# digital_clock_no_res.net
KiCad netlist of a schematic drawn in EasyEDA
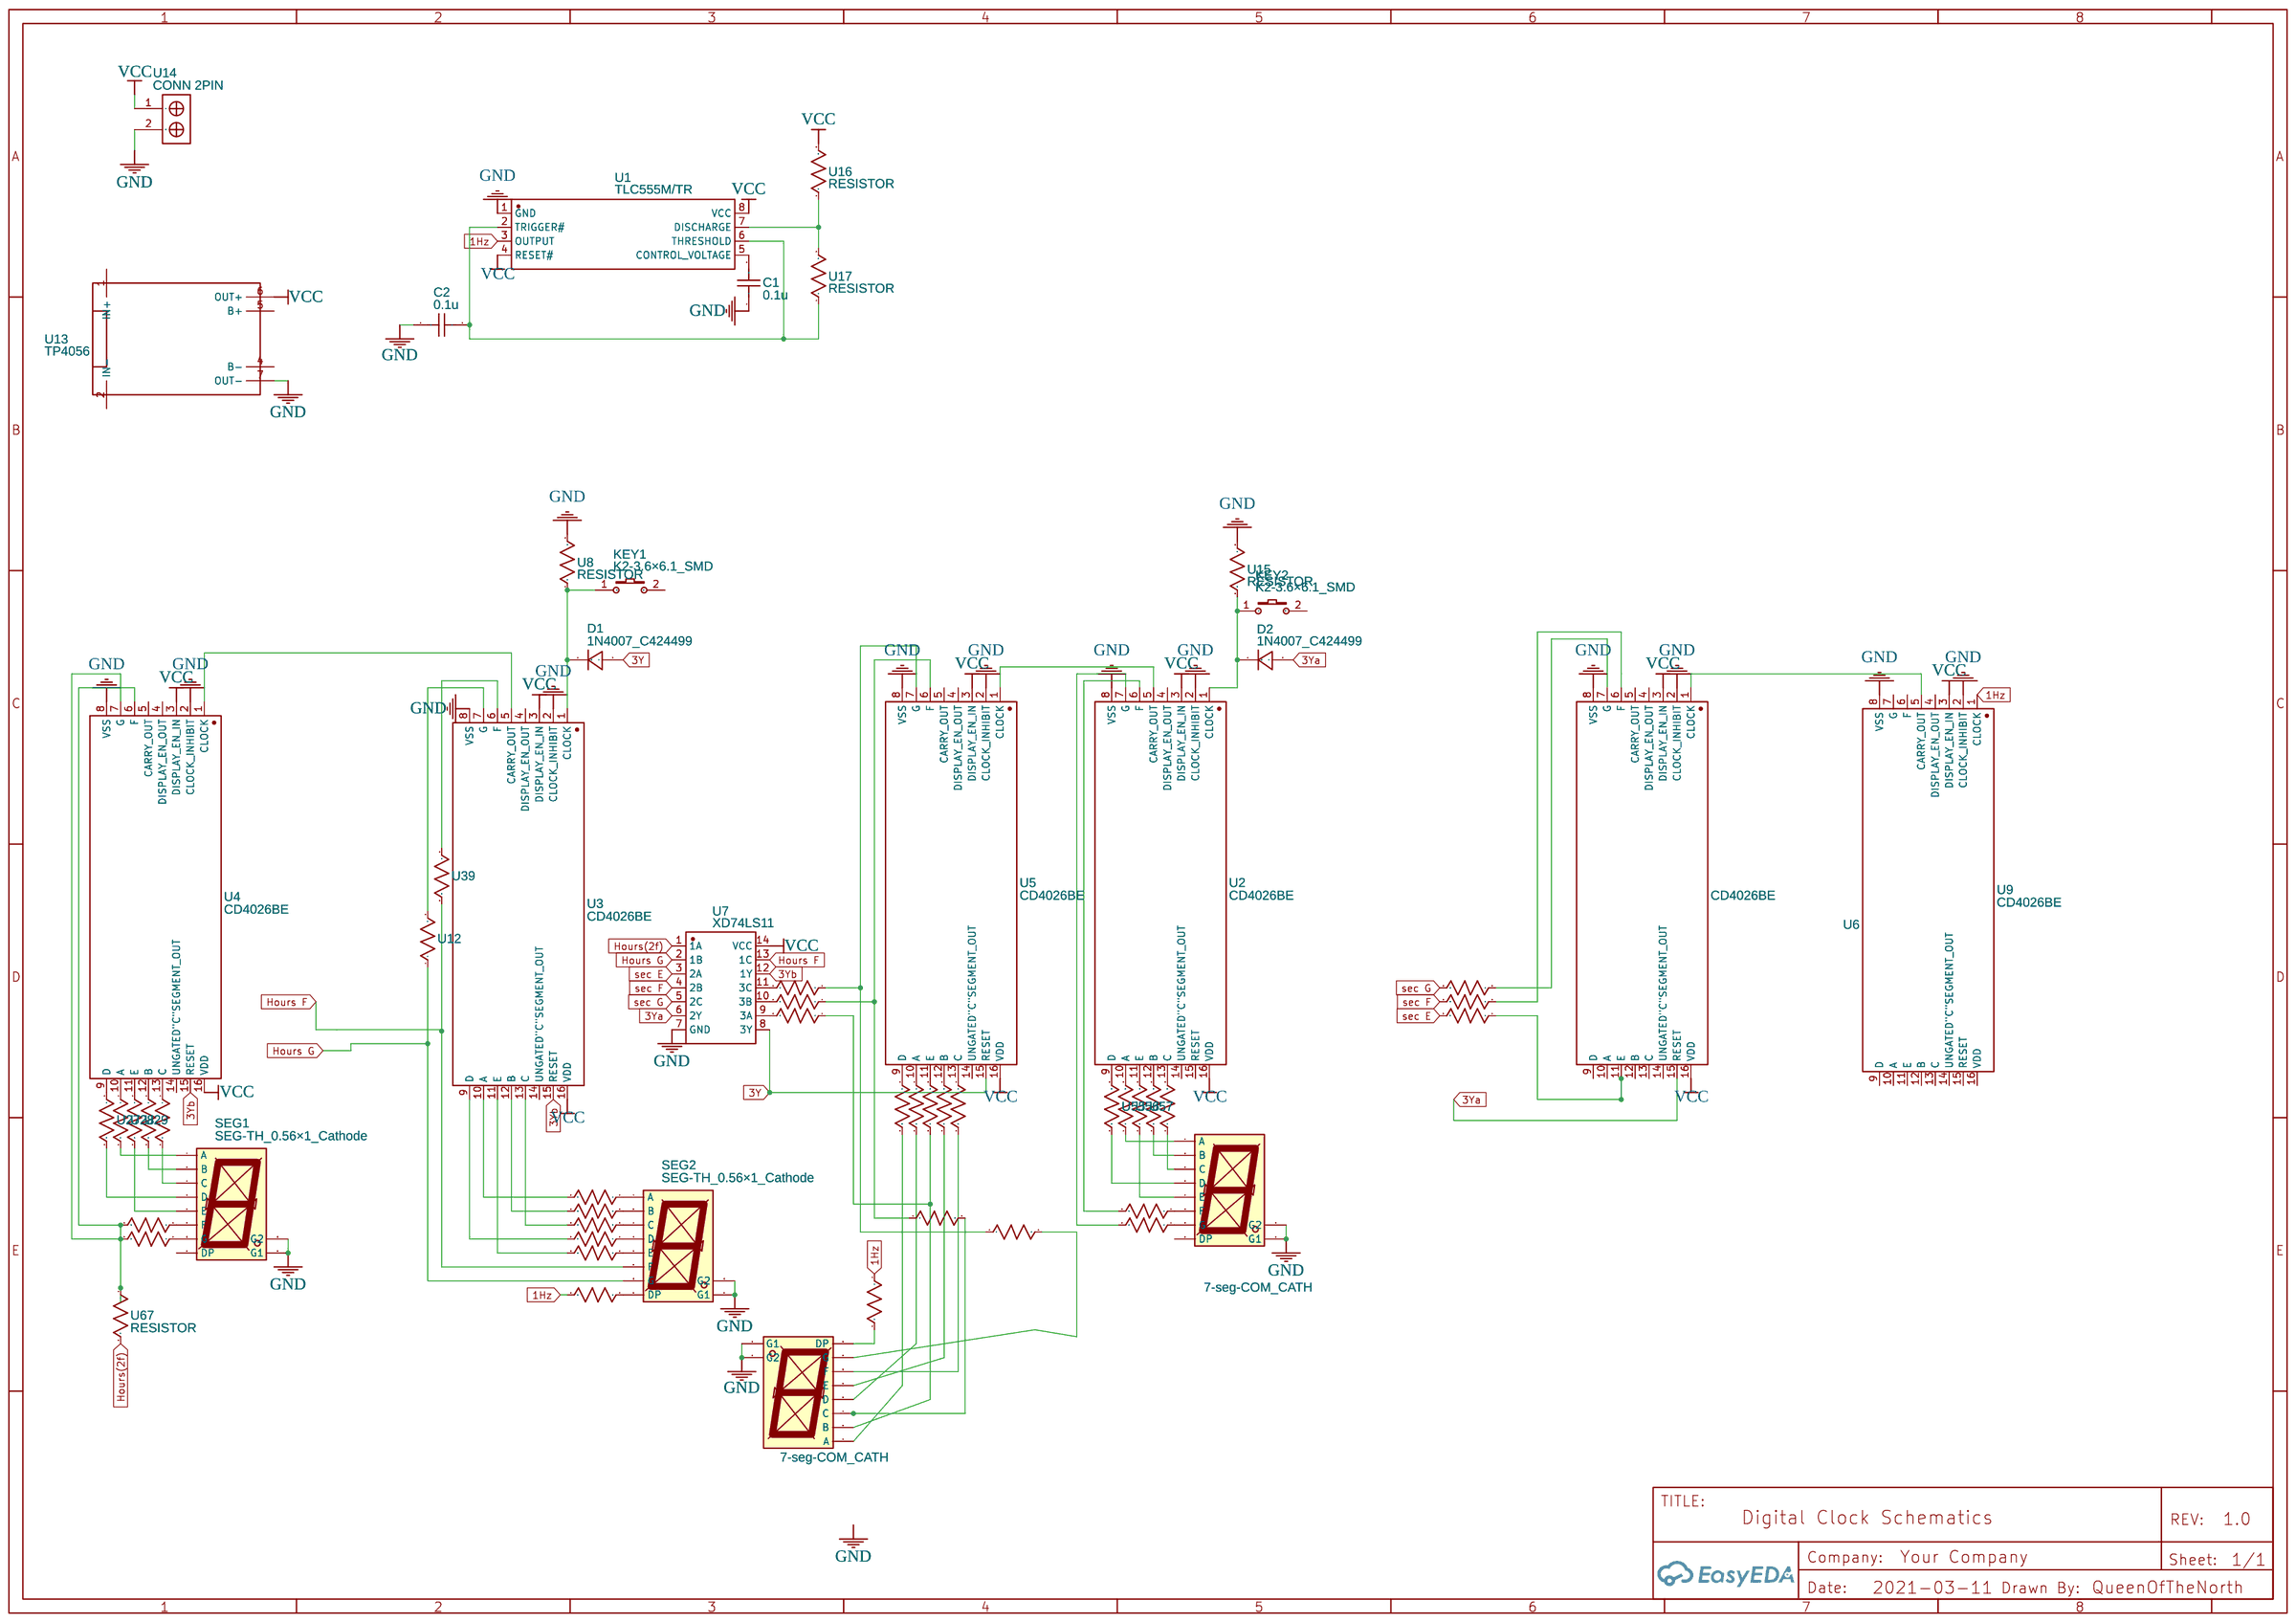
[diagram p0: schematic sheet]

(export (version "E")
  (design (tool "Eeschema 10.0.6"))
  (components
    (comp (ref "C1") (value "0.1u") (libsource (lib "") (part "C_0603_US")))
    (comp (ref "C2") (value "0.1u") (libsource (lib "") (part "C_0603_US_1")))
    (comp (ref "D1")
      (value "1N4007_C424499")
      (fields (field (name "BOM_Manufacturer Part") "1N4007") (field (name "BOM_Supplier Part") "C424499"))
      (libsource (lib "") (part "1N4007_C424499"))
    )
    (comp (ref "D2")
      (value "1N4007_C424499")
      (fields (field (name "BOM_Manufacturer Part") "1N4007") (field (name "BOM_Supplier Part") "C424499"))
      (libsource (lib "") (part "1N4007_C424499"))
    )
    (comp (ref "KEY1")
      (value "K2-3.6×6.1_SMD")
      (fields
        (field (name "BOM_Manufacturer Part") "K2-1107ST-A4SW-06")
        (field (name "BOM_Supplier Part") "C118141")
      )
      (libsource (lib "") (part "K2-3.6×6.1_SMD"))
    )
    (comp (ref "KEY2")
      (value "K2-3.6×6.1_SMD")
      (fields
        (field (name "BOM_Manufacturer Part") "K2-1107ST-A4SW-06")
        (field (name "BOM_Supplier Part") "C118141")
      )
      (libsource (lib "") (part "K2-3.6×6.1_SMD"))
    )
    (comp (ref "SEG1")
      (value "SEG-TH_0.56×1_Cathode")
      (fields (field (name "BOM_Supplier Part") "C8093"))
      (libsource (lib "") (part "SEG-TH_0.56×1_Cathode"))
    )
    (comp (ref "SEG2")
      (value "SEG-TH_0.56×1_Cathode")
      (fields (field (name "BOM_Supplier Part") "C8093"))
      (libsource (lib "") (part "SEG-TH_0.56×1_Cathode"))
    )
    (comp (ref "SEG3")
      (value "7-seg-COM_CATH")
      (fields (field (name "BOM_Supplier Part") "C8093"))
      (libsource (lib "") (part "SEG-TH_0.56×1_Cathode_1"))
    )
    (comp (ref "SEG4")
      (value "7-seg-COM_CATH")
      (fields (field (name "BOM_Supplier Part") "C8093"))
      (libsource (lib "") (part "SEG-TH_0.56×1_Cathode"))
    )
    (comp (ref "U1")
      (value "TLC555M/TR")
      (fields (field (name "BOM_Supplier Part") "C383061"))
      (libsource (lib "") (part "TLC555M/TR"))
    )
    (comp (ref "U2")
      (value "CD4026BE")
      (fields (field (name "BOM_Supplier Part") "C89909"))
      (libsource (lib "") (part "CD4026BE"))
    )
    (comp (ref "U3")
      (value "CD4026BE")
      (fields (field (name "BOM_Supplier Part") "C89909"))
      (libsource (lib "") (part "CD4026BE"))
    )
    (comp (ref "U4")
      (value "CD4026BE")
      (fields (field (name "BOM_Supplier Part") "C89909"))
      (libsource (lib "") (part "CD4026BE"))
    )
    (comp (ref "U5")
      (value "CD4026BE")
      (fields (field (name "BOM_Supplier Part") "C89909"))
      (libsource (lib "") (part "CD4026BE"))
    )
    (comp (ref "U6")
      (value "CD4026BE")
      (fields (field (name "BOM_Supplier Part") "C89909"))
      (libsource (lib "") (part "CD4026BE"))
    )
    (comp (ref "U7")
      (value "XD74LS11")
      (fields (field (name "BOM_Supplier Part") "C521167"))
      (libsource (lib "") (part "XD74LS11"))
    )
    (comp (ref "U8")
      (value "RESISTOR")
      (fields (field (name "BOM_Manufacturer Part") "0.4W 1% RESISTOR"))
      (libsource (lib "") (part "RESISTOR"))
    )
    (comp (ref "U9")
      (value "CD4026BE")
      (fields (field (name "BOM_Supplier Part") "C89909"))
      (libsource (lib "") (part "CD4026BE"))
    )
    (comp (ref "U10")
      (value "RESISTOR")
      (fields (field (name "BOM_Manufacturer Part") "0.4W 1% RESISTOR"))
      (libsource (lib "") (part "RESISTOR_7"))
    )
    (comp (ref "U11")
      (value "RESISTOR")
      (fields (field (name "BOM_Manufacturer Part") "0.4W 1% RESISTOR"))
      (libsource (lib "") (part "RESISTOR_3"))
    )
    (comp (ref "U12")
      (value "RESISTOR")
      (fields (field (name "BOM_Manufacturer Part") "0.4W 1% RESISTOR"))
      (libsource (lib "") (part "RESISTOR_2"))
    )
    (comp (ref "U13")
      (value "TP4056")
      (fields (field (name "BOM_Manufacturer Part") "TP4056-protect"))
      (libsource (lib "") (part "TP4056"))
    )
    (comp (ref "U14")
      (value "CONN 2PIN")
      (fields
        (field (name "BOM_Manufacturer Part") "Terminal Block")
        (field (name "BOM_Supplier Part") "undefined")
      )
      (libsource (lib "") (part "CONN 2PIN"))
    )
    (comp (ref "U15")
      (value "RESISTOR")
      (fields (field (name "BOM_Manufacturer Part") "0.4W 1% RESISTOR"))
      (libsource (lib "") (part "RESISTOR"))
    )
    (comp (ref "U16")
      (value "RESISTOR")
      (fields (field (name "BOM_Manufacturer Part") "0.4W 1% RESISTOR"))
      (libsource (lib "") (part "RESISTOR"))
    )
    (comp (ref "U17")
      (value "RESISTOR")
      (fields (field (name "BOM_Manufacturer Part") "0.4W 1% RESISTOR"))
      (libsource (lib "") (part "RESISTOR"))
    )
    (comp (ref "U18")
      (value "RESISTOR")
      (fields (field (name "BOM_Manufacturer Part") "0.4W 1% RESISTOR"))
      (libsource (lib "") (part "RESISTOR_3"))
    )
    (comp (ref "U19")
      (value "RESISTOR")
      (fields (field (name "BOM_Manufacturer Part") "0.4W 1% RESISTOR"))
      (libsource (lib "") (part "RESISTOR_3"))
    )
    (comp (ref "U20")
      (value "RESISTOR")
      (fields (field (name "BOM_Manufacturer Part") "0.4W 1% RESISTOR"))
      (libsource (lib "") (part "RESISTOR_3"))
    )
    (comp (ref "U21")
      (value "RESISTOR")
      (fields (field (name "BOM_Manufacturer Part") "0.4W 1% RESISTOR"))
      (libsource (lib "") (part "RESISTOR_3"))
    )
    (comp (ref "U22")
      (value "RESISTOR")
      (fields (field (name "BOM_Manufacturer Part") "0.4W 1% RESISTOR"))
      (libsource (lib "") (part "RESISTOR_3"))
    )
    (comp (ref "U25")
      (value "RESISTOR")
      (fields (field (name "BOM_Manufacturer Part") "0.4W 1% RESISTOR"))
      (libsource (lib "") (part "RESISTOR_3"))
    )
    (comp (ref "U26")
      (value "RESISTOR")
      (fields (field (name "BOM_Manufacturer Part") "0.4W 1% RESISTOR"))
      (libsource (lib "") (part "RESISTOR_3"))
    )
    (comp (ref "U27")
      (value "RESISTOR")
      (fields (field (name "BOM_Manufacturer Part") "0.4W 1% RESISTOR"))
      (libsource (lib "") (part "RESISTOR_4"))
    )
    (comp (ref "U28")
      (value "RESISTOR")
      (fields (field (name "BOM_Manufacturer Part") "0.4W 1% RESISTOR"))
      (libsource (lib "") (part "RESISTOR_4"))
    )
    (comp (ref "U29")
      (value "RESISTOR")
      (fields (field (name "BOM_Manufacturer Part") "0.4W 1% RESISTOR"))
      (libsource (lib "") (part "RESISTOR_4"))
    )
    (comp (ref "U30")
      (value "RESISTOR")
      (fields (field (name "BOM_Manufacturer Part") "0.4W 1% RESISTOR"))
      (libsource (lib "") (part "RESISTOR_4"))
    )
    (comp (ref "U31")
      (value "RESISTOR")
      (fields (field (name "BOM_Manufacturer Part") "0.4W 1% RESISTOR"))
      (libsource (lib "") (part "RESISTOR_4"))
    )
    (comp (ref "U32")
      (value "RESISTOR")
      (fields (field (name "BOM_Manufacturer Part") "0.4W 1% RESISTOR"))
      (libsource (lib "") (part "RESISTOR_4"))
    )
    (comp (ref "U33")
      (value "RESISTOR")
      (fields (field (name "BOM_Manufacturer Part") "0.4W 1% RESISTOR"))
      (libsource (lib "") (part "RESISTOR_4"))
    )
    (comp (ref "U34")
      (value "RESISTOR")
      (fields (field (name "BOM_Manufacturer Part") "0.4W 1% RESISTOR"))
      (libsource (lib "") (part "RESISTOR_4"))
    )
    (comp (ref "U35")
      (value "RESISTOR")
      (fields (field (name "BOM_Manufacturer Part") "0.4W 1% RESISTOR"))
      (libsource (lib "") (part "RESISTOR_4"))
    )
    (comp (ref "U36")
      (value "RESISTOR")
      (fields (field (name "BOM_Manufacturer Part") "0.4W 1% RESISTOR"))
      (libsource (lib "") (part "RESISTOR_4"))
    )
    (comp (ref "U37")
      (value "RESISTOR")
      (fields (field (name "BOM_Manufacturer Part") "0.4W 1% RESISTOR"))
      (libsource (lib "") (part "RESISTOR_1"))
    )
    (comp (ref "U38")
      (value "RESISTOR")
      (fields (field (name "BOM_Manufacturer Part") "0.4W 1% RESISTOR"))
      (libsource (lib "") (part "RESISTOR_1"))
    )
    (comp (ref "U39")
      (value "RESISTOR")
      (fields (field (name "BOM_Manufacturer Part") "0.4W 1% RESISTOR"))
      (libsource (lib "") (part "RESISTOR_2"))
    )
    (comp (ref "U52")
      (value "RESISTOR")
      (fields (field (name "BOM_Manufacturer Part") "0.4W 1% RESISTOR"))
      (libsource (lib "") (part "RESISTOR_3"))
    )
    (comp (ref "U53")
      (value "RESISTOR")
      (fields (field (name "BOM_Manufacturer Part") "0.4W 1% RESISTOR"))
      (libsource (lib "") (part "RESISTOR_3"))
    )
    (comp (ref "U54")
      (value "RESISTOR")
      (fields (field (name "BOM_Manufacturer Part") "0.4W 1% RESISTOR"))
      (libsource (lib "") (part "RESISTOR_3"))
    )
    (comp (ref "U55")
      (value "RESISTOR")
      (fields (field (name "BOM_Manufacturer Part") "0.4W 1% RESISTOR"))
      (libsource (lib "") (part "RESISTOR"))
    )
    (comp (ref "U56")
      (value "RESISTOR")
      (fields (field (name "BOM_Manufacturer Part") "0.4W 1% RESISTOR"))
      (libsource (lib "") (part "RESISTOR"))
    )
    (comp (ref "U57")
      (value "RESISTOR")
      (fields (field (name "BOM_Manufacturer Part") "0.4W 1% RESISTOR"))
      (libsource (lib "") (part "RESISTOR"))
    )
    (comp (ref "U58")
      (value "RESISTOR")
      (fields (field (name "BOM_Manufacturer Part") "0.4W 1% RESISTOR"))
      (libsource (lib "") (part "RESISTOR"))
    )
    (comp (ref "U59")
      (value "RESISTOR")
      (fields (field (name "BOM_Manufacturer Part") "0.4W 1% RESISTOR"))
      (libsource (lib "") (part "RESISTOR"))
    )
    (comp (ref "U60")
      (value "RESISTOR")
      (fields (field (name "BOM_Manufacturer Part") "0.4W 1% RESISTOR"))
      (libsource (lib "") (part "RESISTOR_3"))
    )
    (comp (ref "U61")
      (value "RESISTOR")
      (fields (field (name "BOM_Manufacturer Part") "0.4W 1% RESISTOR"))
      (libsource (lib "") (part "RESISTOR_3"))
    )
    (comp (ref "U62")
      (value "RESISTOR")
      (fields (field (name "BOM_Manufacturer Part") "0.4W 1% RESISTOR"))
      (libsource (lib "") (part "RESISTOR_5"))
    )
    (comp (ref "U63")
      (value "RESISTOR")
      (fields (field (name "BOM_Manufacturer Part") "0.4W 1% RESISTOR"))
      (libsource (lib "") (part "RESISTOR_5"))
    )
    (comp (ref "U64")
      (value "RESISTOR")
      (fields (field (name "BOM_Manufacturer Part") "0.4W 1% RESISTOR"))
      (libsource (lib "") (part "RESISTOR_5"))
    )
    (comp (ref "U67")
      (value "RESISTOR")
      (fields (field (name "BOM_Manufacturer Part") "0.4W 1% RESISTOR"))
      (libsource (lib "") (part "RESISTOR_6"))
    )
  )
  (nets
    (net (code "1") (name "1Hz") (class "Default")
      (node (ref "U1") (pin "3") (pinfunction "OUTPUT_3") (pintype "unspecified"))
      (node (ref "U10") (pin "1") (pinfunction "1_1") (pintype "unspecified"))
      (node (ref "U11") (pin "2") (pinfunction "2_2") (pintype "unspecified"))
      (node (ref "U9") (pin "1") (pinfunction "CLOCK_1") (pintype "unspecified"))
    )
    (net (code "2") (name "3Y") (class "Default")
      (node (ref "D1") (pin "2") (pinfunction "A_2") (pintype "unspecified"))
      (node (ref "U5") (pin "15") (pinfunction "RESET_15") (pintype "unspecified"))
      (node (ref "U7") (pin "8") (pinfunction "3Y_8") (pintype "unspecified"))
    )
    (net (code "3") (name "3Ya") (class "Default")
      (node (ref "D2") (pin "2") (pinfunction "A_2") (pintype "unspecified"))
      (node (ref "U6") (pin "15") (pinfunction "RESET_15") (pintype "unspecified"))
      (node (ref "U7") (pin "6") (pinfunction "2Y_6") (pintype "unspecified"))
    )
    (net (code "4") (name "3Yb") (class "Default")
      (node (ref "U3") (pin "15") (pinfunction "RESET_15") (pintype "unspecified"))
      (node (ref "U4") (pin "15") (pinfunction "RESET_15") (pintype "unspecified"))
      (node (ref "U7") (pin "12") (pinfunction "1Y_12") (pintype "unspecified"))
    )
    (net (code "5") (name "GND") (class "Default")
      (node (ref "C1") (pin "1") (pinfunction "1_1") (pintype "unspecified"))
      (node (ref "C2") (pin "1") (pinfunction "1_1") (pintype "unspecified"))
      (node (ref "SEG1") (pin "3") (pinfunction "G1_3") (pintype "unspecified"))
      (node (ref "SEG1") (pin "8") (pinfunction "G2_8") (pintype "unspecified"))
      (node (ref "SEG2") (pin "3") (pinfunction "G1_3") (pintype "unspecified"))
      (node (ref "SEG2") (pin "8") (pinfunction "G2_8") (pintype "unspecified"))
      (node (ref "SEG3") (pin "3") (pinfunction "G1_3") (pintype "unspecified"))
      (node (ref "SEG3") (pin "8") (pinfunction "G2_8") (pintype "unspecified"))
      (node (ref "SEG4") (pin "3") (pinfunction "G1_3") (pintype "unspecified"))
      (node (ref "SEG4") (pin "8") (pinfunction "G2_8") (pintype "unspecified"))
      (node (ref "U1") (pin "1") (pinfunction "GND_1") (pintype "unspecified"))
      (node (ref "U13") (pin "7") (pinfunction "OUT-_7") (pintype "unspecified"))
      (node (ref "U14") (pin "2") (pinfunction "2_2") (pintype "unspecified"))
      (node (ref "U15") (pin "2") (pinfunction "2_2") (pintype "unspecified"))
      (node (ref "U2") (pin "2") (pinfunction "CLOCK_INHIBIT_2") (pintype "unspecified"))
      (node (ref "U2") (pin "8") (pinfunction "VSS_8") (pintype "unspecified"))
      (node (ref "U3") (pin "2") (pinfunction "CLOCK_INHIBIT_2") (pintype "unspecified"))
      (node (ref "U3") (pin "8") (pinfunction "VSS_8") (pintype "unspecified"))
      (node (ref "U4") (pin "2") (pinfunction "CLOCK_INHIBIT_2") (pintype "unspecified"))
      (node (ref "U4") (pin "8") (pinfunction "VSS_8") (pintype "unspecified"))
      (node (ref "U5") (pin "2") (pinfunction "CLOCK_INHIBIT_2") (pintype "unspecified"))
      (node (ref "U5") (pin "8") (pinfunction "VSS_8") (pintype "unspecified"))
      (node (ref "U6") (pin "2") (pinfunction "CLOCK_INHIBIT_2") (pintype "unspecified"))
      (node (ref "U6") (pin "8") (pinfunction "VSS_8") (pintype "unspecified"))
      (node (ref "U7") (pin "7") (pinfunction "GND_7") (pintype "unspecified"))
      (node (ref "U8") (pin "2") (pinfunction "2_2") (pintype "unspecified"))
      (node (ref "U9") (pin "2") (pinfunction "CLOCK_INHIBIT_2") (pintype "unspecified"))
      (node (ref "U9") (pin "8") (pinfunction "VSS_8") (pintype "unspecified"))
    )
    (net (code "6") (name "Hours F") (class "Default")
      (node (ref "SEG2") (pin "9") (pinfunction "F_9") (pintype "unspecified"))
      (node (ref "U39") (pin "1") (pinfunction "1_1") (pintype "unspecified"))
      (node (ref "U7") (pin "13") (pinfunction "1C_13") (pintype "unspecified"))
    )
    (net (code "7") (name "Hours G") (class "Default")
      (node (ref "SEG2") (pin "10") (pinfunction "G_10") (pintype "unspecified"))
      (node (ref "U12") (pin "1") (pinfunction "1_1") (pintype "unspecified"))
      (node (ref "U7") (pin "2") (pinfunction "1B_2") (pintype "unspecified"))
    )
    (net (code "8") (name "Hours(2f)") (class "Default")
      (node (ref "U67") (pin "2") (pinfunction "2_2") (pintype "unspecified"))
      (node (ref "U7") (pin "1") (pinfunction "1A_1") (pintype "unspecified"))
    )
    (net (code "9") (name "Net-(D1-C)") (class "Default")
      (node (ref "D1") (pin "1") (pinfunction "C_1") (pintype "unspecified"))
      (node (ref "KEY1") (pin "1") (pinfunction "1_1") (pintype "unspecified"))
      (node (ref "U3") (pin "1") (pinfunction "CLOCK_1") (pintype "unspecified"))
      (node (ref "U8") (pin "1") (pinfunction "1_1") (pintype "unspecified"))
    )
    (net (code "10") (name "Net-(D2-C)") (class "Default")
      (node (ref "D2") (pin "1") (pinfunction "C_1") (pintype "unspecified"))
      (node (ref "KEY2") (pin "1") (pinfunction "1_1") (pintype "unspecified"))
      (node (ref "U15") (pin "1") (pinfunction "1_1") (pintype "unspecified"))
      (node (ref "U2") (pin "1") (pinfunction "CLOCK_1") (pintype "unspecified"))
    )
    (net (code "11") (name "Net-(SEG1-A)") (class "Default")
      (node (ref "SEG1") (pin "7") (pinfunction "A_7") (pintype "unspecified"))
      (node (ref "U28") (pin "2") (pinfunction "2_2") (pintype "unspecified"))
    )
    (net (code "12") (name "Net-(SEG1-B)") (class "Default")
      (node (ref "SEG1") (pin "6") (pinfunction "B_6") (pintype "unspecified"))
      (node (ref "U30") (pin "2") (pinfunction "2_2") (pintype "unspecified"))
    )
    (net (code "13") (name "Net-(SEG1-C)") (class "Default")
      (node (ref "SEG1") (pin "4") (pinfunction "C_4") (pintype "unspecified"))
      (node (ref "U31") (pin "2") (pinfunction "2_2") (pintype "unspecified"))
    )
    (net (code "14") (name "Net-(SEG1-D)") (class "Default")
      (node (ref "SEG1") (pin "2") (pinfunction "D_2") (pintype "unspecified"))
      (node (ref "U27") (pin "2") (pinfunction "2_2") (pintype "unspecified"))
    )
    (net (code "15") (name "Net-(SEG1-E)") (class "Default")
      (node (ref "SEG1") (pin "1") (pinfunction "E_1") (pintype "unspecified"))
      (node (ref "U29") (pin "2") (pinfunction "2_2") (pintype "unspecified"))
    )
    (net (code "16") (name "Net-(SEG1-F)") (class "Default")
      (node (ref "SEG1") (pin "9") (pinfunction "F_9") (pintype "unspecified"))
      (node (ref "U26") (pin "1") (pinfunction "1_1") (pintype "unspecified"))
    )
    (net (code "17") (name "Net-(SEG1-G)") (class "Default")
      (node (ref "SEG1") (pin "10") (pinfunction "G_10") (pintype "unspecified"))
      (node (ref "U25") (pin "1") (pinfunction "1_1") (pintype "unspecified"))
    )
    (net (code "18") (name "Net-(SEG2-A)") (class "Default")
      (node (ref "SEG2") (pin "7") (pinfunction "A_7") (pintype "unspecified"))
      (node (ref "U18") (pin "1") (pinfunction "1_1") (pintype "unspecified"))
    )
    (net (code "19") (name "Net-(SEG2-B)") (class "Default")
      (node (ref "SEG2") (pin "6") (pinfunction "B_6") (pintype "unspecified"))
      (node (ref "U19") (pin "1") (pinfunction "1_1") (pintype "unspecified"))
    )
    (net (code "20") (name "Net-(SEG2-C)") (class "Default")
      (node (ref "SEG2") (pin "4") (pinfunction "C_4") (pintype "unspecified"))
      (node (ref "U20") (pin "1") (pinfunction "1_1") (pintype "unspecified"))
    )
    (net (code "21") (name "Net-(SEG2-D)") (class "Default")
      (node (ref "SEG2") (pin "2") (pinfunction "D_2") (pintype "unspecified"))
      (node (ref "U21") (pin "1") (pinfunction "1_1") (pintype "unspecified"))
    )
    (net (code "22") (name "Net-(SEG2-DP)") (class "Default")
      (node (ref "SEG2") (pin "5") (pinfunction "DP_5") (pintype "unspecified"))
      (node (ref "U11") (pin "1") (pinfunction "1_1") (pintype "unspecified"))
    )
    (net (code "23") (name "Net-(SEG2-E)") (class "Default")
      (node (ref "SEG2") (pin "1") (pinfunction "E_1") (pintype "unspecified"))
      (node (ref "U22") (pin "1") (pinfunction "1_1") (pintype "unspecified"))
    )
    (net (code "24") (name "Net-(SEG3-A)") (class "Default")
      (node (ref "SEG3") (pin "7") (pinfunction "A_7") (pintype "unspecified"))
      (node (ref "U36") (pin "2") (pinfunction "2_2") (pintype "unspecified"))
    )
    (net (code "25") (name "Net-(SEG3-B)") (class "Default")
      (node (ref "SEG3") (pin "6") (pinfunction "B_6") (pintype "unspecified"))
      (node (ref "U34") (pin "2") (pinfunction "2_2") (pintype "unspecified"))
      (node (ref "U64") (pin "1") (pinfunction "1_1") (pintype "unspecified"))
    )
    (net (code "26") (name "Net-(SEG3-C)") (class "Default")
      (node (ref "SEG3") (pin "4") (pinfunction "C_4") (pintype "unspecified"))
      (node (ref "U37") (pin "2") (pinfunction "2_2") (pintype "unspecified"))
    )
    (net (code "27") (name "Net-(SEG3-D)") (class "Default")
      (node (ref "SEG3") (pin "2") (pinfunction "D_2") (pintype "unspecified"))
      (node (ref "U35") (pin "2") (pinfunction "2_2") (pintype "unspecified"))
    )
    (net (code "28") (name "Net-(SEG3-DP)") (class "Default")
      (node (ref "SEG3") (pin "5") (pinfunction "DP_5") (pintype "unspecified"))
      (node (ref "U10") (pin "2") (pinfunction "2_2") (pintype "unspecified"))
    )
    (net (code "29") (name "Net-(SEG3-E)") (class "Default")
      (node (ref "SEG3") (pin "1") (pinfunction "E_1") (pintype "unspecified"))
      (node (ref "U33") (pin "2") (pinfunction "2_2") (pintype "unspecified"))
    )
    (net (code "30") (name "Net-(SEG3-F)") (class "Default")
      (node (ref "SEG3") (pin "9") (pinfunction "F_9") (pintype "unspecified"))
      (node (ref "U32") (pin "2") (pinfunction "2_2") (pintype "unspecified"))
    )
    (net (code "31") (name "Net-(SEG3-G)") (class "Default")
      (node (ref "SEG3") (pin "10") (pinfunction "G_10") (pintype "unspecified"))
      (node (ref "U38") (pin "2") (pinfunction "2_2") (pintype "unspecified"))
    )
    (net (code "32") (name "Net-(SEG4-A)") (class "Default")
      (node (ref "SEG4") (pin "7") (pinfunction "A_7") (pintype "unspecified"))
      (node (ref "U56") (pin "1") (pinfunction "1_1") (pintype "unspecified"))
    )
    (net (code "33") (name "Net-(SEG4-B)") (class "Default")
      (node (ref "SEG4") (pin "6") (pinfunction "B_6") (pintype "unspecified"))
      (node (ref "U58") (pin "1") (pinfunction "1_1") (pintype "unspecified"))
    )
    (net (code "34") (name "Net-(SEG4-C)") (class "Default")
      (node (ref "SEG4") (pin "4") (pinfunction "C_4") (pintype "unspecified"))
      (node (ref "U59") (pin "1") (pinfunction "1_1") (pintype "unspecified"))
    )
    (net (code "35") (name "Net-(SEG4-D)") (class "Default")
      (node (ref "SEG4") (pin "2") (pinfunction "D_2") (pintype "unspecified"))
      (node (ref "U55") (pin "1") (pinfunction "1_1") (pintype "unspecified"))
    )
    (net (code "36") (name "Net-(SEG4-E)") (class "Default")
      (node (ref "SEG4") (pin "1") (pinfunction "E_1") (pintype "unspecified"))
      (node (ref "U57") (pin "1") (pinfunction "1_1") (pintype "unspecified"))
    )
    (net (code "37") (name "Net-(SEG4-F)") (class "Default")
      (node (ref "SEG4") (pin "9") (pinfunction "F_9") (pintype "unspecified"))
      (node (ref "U61") (pin "1") (pinfunction "1_1") (pintype "unspecified"))
    )
    (net (code "38") (name "Net-(SEG4-G)") (class "Default")
      (node (ref "SEG4") (pin "10") (pinfunction "G_10") (pintype "unspecified"))
      (node (ref "U60") (pin "1") (pinfunction "1_1") (pintype "unspecified"))
    )
    (net (code "39") (name "Net-(U1-CONTROL_VOLTAGE)") (class "Default")
      (node (ref "C1") (pin "2") (pinfunction "2_2") (pintype "unspecified"))
      (node (ref "U1") (pin "5") (pinfunction "CONTROL_VOLTAGE_5") (pintype "unspecified"))
    )
    (net (code "40") (name "Net-(U1-DISCHARGE)") (class "Default")
      (node (ref "U1") (pin "7") (pinfunction "DISCHARGE_7") (pintype "unspecified"))
      (node (ref "U16") (pin "1") (pinfunction "1_1") (pintype "unspecified"))
      (node (ref "U17") (pin "2") (pinfunction "2_2") (pintype "unspecified"))
    )
    (net (code "41") (name "Net-(U1-THRESHOLD)") (class "Default")
      (node (ref "C2") (pin "2") (pinfunction "2_2") (pintype "unspecified"))
      (node (ref "U1") (pin "2") (pinfunction "TRIGGER#_2") (pintype "unspecified"))
      (node (ref "U1") (pin "6") (pinfunction "THRESHOLD_6") (pintype "unspecified"))
      (node (ref "U17") (pin "1") (pinfunction "1_1") (pintype "unspecified"))
    )
    (net (code "42") (name "Net-(U2-A)") (class "Default")
      (node (ref "U2") (pin "10") (pinfunction "A_10") (pintype "unspecified"))
      (node (ref "U56") (pin "2") (pinfunction "2_2") (pintype "unspecified"))
    )
    (net (code "43") (name "Net-(U2-B)") (class "Default")
      (node (ref "U2") (pin "12") (pinfunction "B_12") (pintype "unspecified"))
      (node (ref "U58") (pin "2") (pinfunction "2_2") (pintype "unspecified"))
    )
    (net (code "44") (name "Net-(U2-C)") (class "Default")
      (node (ref "U2") (pin "13") (pinfunction "C_13") (pintype "unspecified"))
      (node (ref "U59") (pin "2") (pinfunction "2_2") (pintype "unspecified"))
    )
    (net (code "45") (name "Net-(U2-CARRY_OUT)") (class "Default")
      (node (ref "U2") (pin "5") (pinfunction "CARRY_OUT_5") (pintype "unspecified"))
      (node (ref "U5") (pin "1") (pinfunction "CLOCK_1") (pintype "unspecified"))
    )
    (net (code "46") (name "Net-(U2-D)") (class "Default")
      (node (ref "U2") (pin "9") (pinfunction "D_9") (pintype "unspecified"))
      (node (ref "U55") (pin "2") (pinfunction "2_2") (pintype "unspecified"))
    )
    (net (code "47") (name "Net-(U2-E)") (class "Default")
      (node (ref "U2") (pin "11") (pinfunction "E_11") (pintype "unspecified"))
      (node (ref "U57") (pin "2") (pinfunction "2_2") (pintype "unspecified"))
    )
    (net (code "48") (name "Net-(U2-F)") (class "Default")
      (node (ref "U2") (pin "6") (pinfunction "F_6") (pintype "unspecified"))
      (node (ref "U61") (pin "2") (pinfunction "2_2") (pintype "unspecified"))
    )
    (net (code "49") (name "Net-(U2-G)") (class "Default")
      (node (ref "U2") (pin "7") (pinfunction "G_7") (pintype "unspecified"))
      (node (ref "U60") (pin "2") (pinfunction "2_2") (pintype "unspecified"))
    )
    (net (code "50") (name "Net-(U3-A)") (class "Default")
      (node (ref "U18") (pin "2") (pinfunction "2_2") (pintype "unspecified"))
      (node (ref "U3") (pin "10") (pinfunction "A_10") (pintype "unspecified"))
    )
    (net (code "51") (name "Net-(U3-B)") (class "Default")
      (node (ref "U19") (pin "2") (pinfunction "2_2") (pintype "unspecified"))
      (node (ref "U3") (pin "12") (pinfunction "B_12") (pintype "unspecified"))
    )
    (net (code "52") (name "Net-(U3-C)") (class "Default")
      (node (ref "U20") (pin "2") (pinfunction "2_2") (pintype "unspecified"))
      (node (ref "U3") (pin "13") (pinfunction "C_13") (pintype "unspecified"))
    )
    (net (code "53") (name "Net-(U3-CARRY_OUT)") (class "Default")
      (node (ref "U3") (pin "5") (pinfunction "CARRY_OUT_5") (pintype "unspecified"))
      (node (ref "U4") (pin "1") (pinfunction "CLOCK_1") (pintype "unspecified"))
    )
    (net (code "54") (name "Net-(U3-D)") (class "Default")
      (node (ref "U21") (pin "2") (pinfunction "2_2") (pintype "unspecified"))
      (node (ref "U3") (pin "9") (pinfunction "D_9") (pintype "unspecified"))
    )
    (net (code "55") (name "Net-(U3-E)") (class "Default")
      (node (ref "U22") (pin "2") (pinfunction "2_2") (pintype "unspecified"))
      (node (ref "U3") (pin "11") (pinfunction "E_11") (pintype "unspecified"))
    )
    (net (code "56") (name "Net-(U3-F)") (class "Default")
      (node (ref "U3") (pin "6") (pinfunction "F_6") (pintype "unspecified"))
      (node (ref "U39") (pin "2") (pinfunction "2_2") (pintype "unspecified"))
    )
    (net (code "57") (name "Net-(U3-G)") (class "Default")
      (node (ref "U12") (pin "2") (pinfunction "2_2") (pintype "unspecified"))
      (node (ref "U3") (pin "7") (pinfunction "G_7") (pintype "unspecified"))
    )
    (net (code "58") (name "Net-(U4-A)") (class "Default")
      (node (ref "U28") (pin "1") (pinfunction "1_1") (pintype "unspecified"))
      (node (ref "U4") (pin "10") (pinfunction "A_10") (pintype "unspecified"))
    )
    (net (code "59") (name "Net-(U4-B)") (class "Default")
      (node (ref "U30") (pin "1") (pinfunction "1_1") (pintype "unspecified"))
      (node (ref "U4") (pin "12") (pinfunction "B_12") (pintype "unspecified"))
    )
    (net (code "60") (name "Net-(U4-C)") (class "Default")
      (node (ref "U31") (pin "1") (pinfunction "1_1") (pintype "unspecified"))
      (node (ref "U4") (pin "13") (pinfunction "C_13") (pintype "unspecified"))
    )
    (net (code "61") (name "Net-(U4-D)") (class "Default")
      (node (ref "U27") (pin "1") (pinfunction "1_1") (pintype "unspecified"))
      (node (ref "U4") (pin "9") (pinfunction "D_9") (pintype "unspecified"))
    )
    (net (code "62") (name "Net-(U4-E)") (class "Default")
      (node (ref "U29") (pin "1") (pinfunction "1_1") (pintype "unspecified"))
      (node (ref "U4") (pin "11") (pinfunction "E_11") (pintype "unspecified"))
    )
    (net (code "63") (name "Net-(U4-F)") (class "Default")
      (node (ref "U25") (pin "2") (pinfunction "2_2") (pintype "unspecified"))
      (node (ref "U26") (pin "2") (pinfunction "2_2") (pintype "unspecified"))
      (node (ref "U4") (pin "6") (pinfunction "F_6") (pintype "unspecified"))
      (node (ref "U4") (pin "7") (pinfunction "G_7") (pintype "unspecified"))
      (node (ref "U67") (pin "1") (pinfunction "1_1") (pintype "unspecified"))
    )
    (net (code "64") (name "Net-(U5-A)") (class "Default")
      (node (ref "U35") (pin "1") (pinfunction "1_1") (pintype "unspecified"))
      (node (ref "U5") (pin "10") (pinfunction "A_10") (pintype "unspecified"))
    )
    (net (code "65") (name "Net-(U5-B)") (class "Default")
      (node (ref "U33") (pin "1") (pinfunction "1_1") (pintype "unspecified"))
      (node (ref "U5") (pin "12") (pinfunction "B_12") (pintype "unspecified"))
    )
    (net (code "66") (name "Net-(U5-C)") (class "Default")
      (node (ref "U32") (pin "1") (pinfunction "1_1") (pintype "unspecified"))
      (node (ref "U5") (pin "13") (pinfunction "C_13") (pintype "unspecified"))
    )
    (net (code "67") (name "Net-(U5-D)") (class "Default")
      (node (ref "U36") (pin "1") (pinfunction "1_1") (pintype "unspecified"))
      (node (ref "U5") (pin "9") (pinfunction "D_9") (pintype "unspecified"))
    )
    (net (code "68") (name "Net-(U5-E)") (class "Default")
      (node (ref "U34") (pin "1") (pinfunction "1_1") (pintype "unspecified"))
      (node (ref "U5") (pin "11") (pinfunction "E_11") (pintype "unspecified"))
    )
    (net (code "69") (name "Net-(U5-F)") (class "Default")
      (node (ref "U37") (pin "1") (pinfunction "1_1") (pintype "unspecified"))
      (node (ref "U5") (pin "6") (pinfunction "F_6") (pintype "unspecified"))
      (node (ref "U63") (pin "1") (pinfunction "1_1") (pintype "unspecified"))
    )
    (net (code "70") (name "Net-(U5-G)") (class "Default")
      (node (ref "U38") (pin "1") (pinfunction "1_1") (pintype "unspecified"))
      (node (ref "U5") (pin "7") (pinfunction "G_7") (pintype "unspecified"))
      (node (ref "U62") (pin "1") (pinfunction "1_1") (pintype "unspecified"))
    )
    (net (code "71") (name "Net-(U6-CLOCK)") (class "Default")
      (node (ref "U6") (pin "1") (pinfunction "CLOCK_1") (pintype "unspecified"))
      (node (ref "U9") (pin "5") (pinfunction "CARRY_OUT_5") (pintype "unspecified"))
    )
    (net (code "72") (name "Net-(U6-E)") (class "Default")
      (node (ref "U52") (pin "1") (pinfunction "1_1") (pintype "unspecified"))
      (node (ref "U6") (pin "11") (pinfunction "E_11") (pintype "unspecified"))
    )
    (net (code "73") (name "Net-(U6-F)") (class "Default")
      (node (ref "U53") (pin "1") (pinfunction "1_1") (pintype "unspecified"))
      (node (ref "U6") (pin "6") (pinfunction "F_6") (pintype "unspecified"))
    )
    (net (code "74") (name "Net-(U6-G)") (class "Default")
      (node (ref "U54") (pin "1") (pinfunction "1_1") (pintype "unspecified"))
      (node (ref "U6") (pin "7") (pinfunction "G_7") (pintype "unspecified"))
    )
    (net (code "75") (name "Net-(U7-3A)") (class "Default")
      (node (ref "U64") (pin "2") (pinfunction "2_2") (pintype "unspecified"))
      (node (ref "U7") (pin "9") (pinfunction "3A_9") (pintype "unspecified"))
    )
    (net (code "76") (name "Net-(U7-3B)") (class "Default")
      (node (ref "U63") (pin "2") (pinfunction "2_2") (pintype "unspecified"))
      (node (ref "U7") (pin "10") (pinfunction "3B_10") (pintype "unspecified"))
    )
    (net (code "77") (name "Net-(U7-3C)") (class "Default")
      (node (ref "U62") (pin "2") (pinfunction "2_2") (pintype "unspecified"))
      (node (ref "U7") (pin "11") (pinfunction "3C_11") (pintype "unspecified"))
    )
    (net (code "78") (name "VCC") (class "Default")
      (node (ref "U1") (pin "4") (pinfunction "RESET#_4") (pintype "unspecified"))
      (node (ref "U1") (pin "8") (pinfunction "VCC_8") (pintype "unspecified"))
      (node (ref "U13") (pin "6") (pinfunction "OUT+_6") (pintype "unspecified"))
      (node (ref "U14") (pin "1") (pinfunction "1_1") (pintype "unspecified"))
      (node (ref "U16") (pin "2") (pinfunction "2_2") (pintype "unspecified"))
      (node (ref "U2") (pin "16") (pinfunction "VDD_16") (pintype "unspecified"))
      (node (ref "U2") (pin "3") (pinfunction "DISPLAY_EN_IN_3") (pintype "unspecified"))
      (node (ref "U3") (pin "16") (pinfunction "VDD_16") (pintype "unspecified"))
      (node (ref "U3") (pin "3") (pinfunction "DISPLAY_EN_IN_3") (pintype "unspecified"))
      (node (ref "U4") (pin "16") (pinfunction "VDD_16") (pintype "unspecified"))
      (node (ref "U4") (pin "3") (pinfunction "DISPLAY_EN_IN_3") (pintype "unspecified"))
      (node (ref "U5") (pin "16") (pinfunction "VDD_16") (pintype "unspecified"))
      (node (ref "U5") (pin "3") (pinfunction "DISPLAY_EN_IN_3") (pintype "unspecified"))
      (node (ref "U6") (pin "16") (pinfunction "VDD_16") (pintype "unspecified"))
      (node (ref "U6") (pin "3") (pinfunction "DISPLAY_EN_IN_3") (pintype "unspecified"))
      (node (ref "U7") (pin "14") (pinfunction "VCC_14") (pintype "unspecified"))
      (node (ref "U9") (pin "3") (pinfunction "DISPLAY_EN_IN_3") (pintype "unspecified"))
    )
    (net (code "79") (name "sec E") (class "Default")
      (node (ref "U52") (pin "2") (pinfunction "2_2") (pintype "unspecified"))
      (node (ref "U7") (pin "3") (pinfunction "2A_3") (pintype "unspecified"))
    )
    (net (code "80") (name "sec F") (class "Default")
      (node (ref "U53") (pin "2") (pinfunction "2_2") (pintype "unspecified"))
      (node (ref "U7") (pin "4") (pinfunction "2B_4") (pintype "unspecified"))
    )
    (net (code "81") (name "sec G") (class "Default")
      (node (ref "U54") (pin "2") (pinfunction "2_2") (pintype "unspecified"))
      (node (ref "U7") (pin "5") (pinfunction "2C_5") (pintype "unspecified"))
    )
    (net (code "82") (name "unconnected-(KEY1-Pad2)") (class "Default")
      (node (ref "KEY1") (pin "2") (pinfunction "2_2") (pintype "unspecified"))
    )
    (net (code "83") (name "unconnected-(KEY2-Pad2)") (class "Default")
      (node (ref "KEY2") (pin "2") (pinfunction "2_2") (pintype "unspecified"))
    )
    (net (code "84") (name "unconnected-(SEG1-DP-Pad5)") (class "Default")
      (node (ref "SEG1") (pin "5") (pinfunction "DP_5") (pintype "unspecified"))
    )
    (net (code "85") (name "unconnected-(SEG4-DP-Pad5)") (class "Default")
      (node (ref "SEG4") (pin "5") (pinfunction "DP_5") (pintype "unspecified"))
    )
    (net (code "86") (name "unconnected-(U2-DISPLAY_EN_OUT-Pad4)") (class "Default")
      (node (ref "U2") (pin "4") (pinfunction "DISPLAY_EN_OUT_4") (pintype "unspecified"))
    )
    (net (code "87") (name "unconnected-(U2-RESET-Pad15)") (class "Default")
      (node (ref "U2") (pin "15") (pinfunction "RESET_15") (pintype "unspecified"))
    )
    (net (code "88") (name "unconnected-(U2-UNGATED\"C\"SEGMENT_OUT-Pad14)") (class "Default")
      (node (ref "U2") (pin "14") (pinfunction "UNGATED\"C\"SEGMENT_OUT_14") (pintype "unspecified"))
    )
    (net (code "89") (name "unconnected-(U3-DISPLAY_EN_OUT-Pad4)") (class "Default")
      (node (ref "U3") (pin "4") (pinfunction "DISPLAY_EN_OUT_4") (pintype "unspecified"))
    )
    (net (code "90") (name "unconnected-(U3-UNGATED\"C\"SEGMENT_OUT-Pad14)") (class "Default")
      (node (ref "U3") (pin "14") (pinfunction "UNGATED\"C\"SEGMENT_OUT_14") (pintype "unspecified"))
    )
    (net (code "91") (name "unconnected-(U4-CARRY_OUT-Pad5)") (class "Default")
      (node (ref "U4") (pin "5") (pinfunction "CARRY_OUT_5") (pintype "unspecified"))
    )
    (net (code "92") (name "unconnected-(U4-DISPLAY_EN_OUT-Pad4)") (class "Default")
      (node (ref "U4") (pin "4") (pinfunction "DISPLAY_EN_OUT_4") (pintype "unspecified"))
    )
    (net (code "93") (name "unconnected-(U4-UNGATED\"C\"SEGMENT_OUT-Pad14)") (class "Default")
      (node (ref "U4") (pin "14") (pinfunction "UNGATED\"C\"SEGMENT_OUT_14") (pintype "unspecified"))
    )
    (net (code "94") (name "unconnected-(U5-CARRY_OUT-Pad5)") (class "Default")
      (node (ref "U5") (pin "5") (pinfunction "CARRY_OUT_5") (pintype "unspecified"))
    )
    (net (code "95") (name "unconnected-(U5-DISPLAY_EN_OUT-Pad4)") (class "Default")
      (node (ref "U5") (pin "4") (pinfunction "DISPLAY_EN_OUT_4") (pintype "unspecified"))
    )
    (net (code "96") (name "unconnected-(U5-UNGATED\"C\"SEGMENT_OUT-Pad14)") (class "Default")
      (node (ref "U5") (pin "14") (pinfunction "UNGATED\"C\"SEGMENT_OUT_14") (pintype "unspecified"))
    )
    (net (code "97") (name "unconnected-(U6-A-Pad10)") (class "Default")
      (node (ref "U6") (pin "10") (pinfunction "A_10") (pintype "unspecified"))
    )
    (net (code "98") (name "unconnected-(U6-B-Pad12)") (class "Default")
      (node (ref "U6") (pin "12") (pinfunction "B_12") (pintype "unspecified"))
    )
    (net (code "99") (name "unconnected-(U6-C-Pad13)") (class "Default")
      (node (ref "U6") (pin "13") (pinfunction "C_13") (pintype "unspecified"))
    )
    (net (code "100") (name "unconnected-(U6-CARRY_OUT-Pad5)") (class "Default")
      (node (ref "U6") (pin "5") (pinfunction "CARRY_OUT_5") (pintype "unspecified"))
    )
    (net (code "101") (name "unconnected-(U6-D-Pad9)") (class "Default")
      (node (ref "U6") (pin "9") (pinfunction "D_9") (pintype "unspecified"))
    )
    (net (code "102") (name "unconnected-(U6-DISPLAY_EN_OUT-Pad4)") (class "Default")
      (node (ref "U6") (pin "4") (pinfunction "DISPLAY_EN_OUT_4") (pintype "unspecified"))
    )
    (net (code "103") (name "unconnected-(U6-UNGATED\"C\"SEGMENT_OUT-Pad14)") (class "Default")
      (node (ref "U6") (pin "14") (pinfunction "UNGATED\"C\"SEGMENT_OUT_14") (pintype "unspecified"))
    )
    (net (code "104") (name "unconnected-(U9-A-Pad10)") (class "Default")
      (node (ref "U9") (pin "10") (pinfunction "A_10") (pintype "unspecified"))
    )
    (net (code "105") (name "unconnected-(U9-B-Pad12)") (class "Default")
      (node (ref "U9") (pin "12") (pinfunction "B_12") (pintype "unspecified"))
    )
    (net (code "106") (name "unconnected-(U9-C-Pad13)") (class "Default")
      (node (ref "U9") (pin "13") (pinfunction "C_13") (pintype "unspecified"))
    )
    (net (code "107") (name "unconnected-(U9-D-Pad9)") (class "Default")
      (node (ref "U9") (pin "9") (pinfunction "D_9") (pintype "unspecified"))
    )
    (net (code "108") (name "unconnected-(U9-DISPLAY_EN_OUT-Pad4)") (class "Default")
      (node (ref "U9") (pin "4") (pinfunction "DISPLAY_EN_OUT_4") (pintype "unspecified"))
    )
    (net (code "109") (name "unconnected-(U9-E-Pad11)") (class "Default")
      (node (ref "U9") (pin "11") (pinfunction "E_11") (pintype "unspecified"))
    )
    (net (code "110") (name "unconnected-(U9-F-Pad6)") (class "Default")
      (node (ref "U9") (pin "6") (pinfunction "F_6") (pintype "unspecified"))
    )
    (net (code "111") (name "unconnected-(U9-G-Pad7)") (class "Default")
      (node (ref "U9") (pin "7") (pinfunction "G_7") (pintype "unspecified"))
    )
    (net (code "112") (name "unconnected-(U9-RESET-Pad15)") (class "Default")
      (node (ref "U9") (pin "15") (pinfunction "RESET_15") (pintype "unspecified"))
    )
    (net (code "113") (name "unconnected-(U9-UNGATED\"C\"SEGMENT_OUT-Pad14)") (class "Default")
      (node (ref "U9") (pin "14") (pinfunction "UNGATED\"C\"SEGMENT_OUT_14") (pintype "unspecified"))
    )
    (net (code "114") (name "unconnected-(U9-VDD-Pad16)") (class "Default")
      (node (ref "U9") (pin "16") (pinfunction "VDD_16") (pintype "unspecified"))
    )
    (net (code "115") (name "unconnected-(U13-B+-Pad5)") (class "Default")
      (node (ref "U13") (pin "5") (pinfunction "B+_5") (pintype "unspecified"))
    )
    (net (code "116") (name "unconnected-(U13-B--Pad4)") (class "Default")
      (node (ref "U13") (pin "4") (pinfunction "B-_4") (pintype "unspecified"))
    )
    (net (code "117") (name "unconnected-(U13-IN+-Pad1)") (class "Default")
      (node (ref "U13") (pin "1") (pinfunction "IN+_1") (pintype "unspecified"))
    )
    (net (code "118") (name "unconnected-(U13-IN--Pad2)") (class "Default")
      (node (ref "U13") (pin "2") (pinfunction "IN-_2") (pintype "unspecified"))
    )
  )
)
